# FAN_Board_Control_v1_040116.net
KiCad netlist of a schematic drawn in Altium Designer
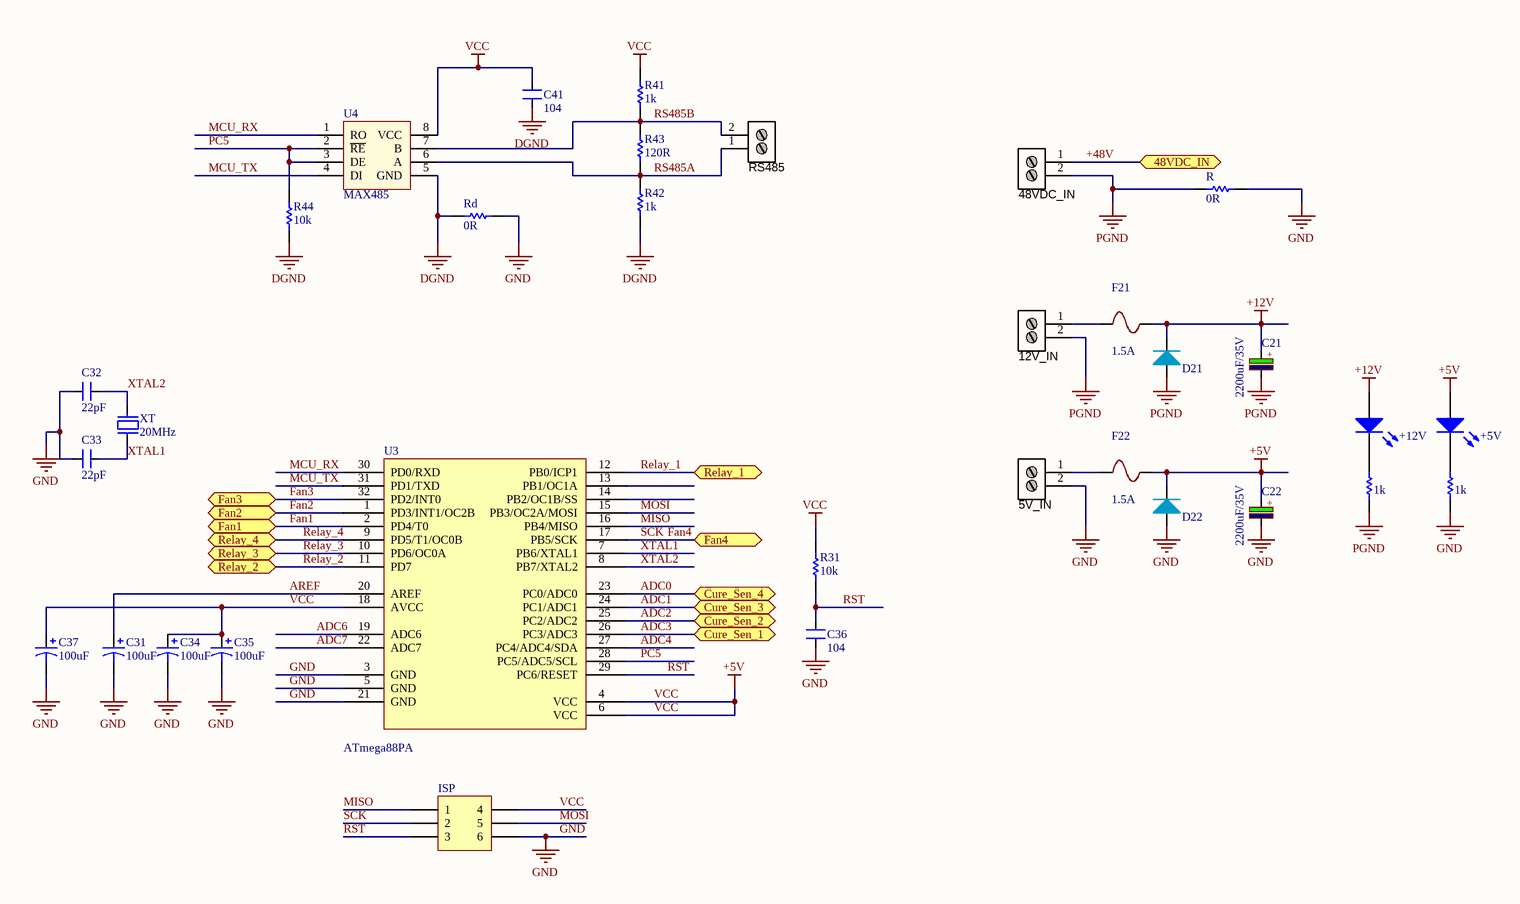
[diagram p0: FAN_Board_Control_v1_040116.SchDoc]

(export (version "E")
  (design (tool "Eeschema 10.0.6"))
  (components
    (comp (ref "+5V") (value "Led") (footprint "LED 5mm RED") (libsource (lib "Tuan") (part "Led")))
    (comp (ref "+12V") (value "Led") (footprint "LED 5mm RED") (libsource (lib "Tuan") (part "Led")))
    (comp (ref "5V_IN")
      (value "Stackable ScrewTerm")
      (footprint "2P_PCB_ScrewTerm_200mil")
      (description "Terminal Block Screw Type THT 2-Position 3.81mm pitch")
      (libsource (lib "PBL - Connectors") (part "2P_ScrewTerm_90S_3.81MM"))
    )
    (comp (ref "12V_IN")
      (value "Stackable ScrewTerm")
      (footprint "2P_PCB_ScrewTerm_200mil")
      (description "Terminal Block Screw Type THT 2-Position 3.81mm pitch")
      (libsource (lib "PBL - Connectors") (part "2P_ScrewTerm_90S_3.81MM"))
    )
    (comp (ref "48VDC_IN")
      (value "Stackable ScrewTerm")
      (footprint "2P_PCB_ScrewTerm_200mil")
      (description "Terminal Block Screw Type THT 2-Position 3.81mm pitch")
      (libsource (lib "PBL - Connectors") (part "2P_ScrewTerm_90S_3.81MM"))
    )
    (comp (ref "C21")
      (value "2200uF/35V")
      (footprint "heromap:CP_1000uF_25V")
      (description "Cap 1000uF/16V - 220uF/50V")
      (libsource (lib "heromap") (part "CP4"))
    )
    (comp (ref "C22")
      (value "2200uF/35V")
      (footprint "heromap:CP_1000uF_25V")
      (description "Cap 1000uF/16V - 220uF/50V")
      (libsource (lib "heromap") (part "CP4"))
    )
    (comp (ref "C31")
      (value "100uF")
      (footprint "CAPC2012N_F")
      (fields (field (name "Comment") "Cap"))
      (libsource (lib "Tuan") (part "Cap"))
    )
    (comp (ref "C32")
      (value "22pF")
      (footprint "CAPC1608N")
      (fields (field (name "Comment") "CAP NP"))
      (libsource (lib "Tuan") (part "CAP NP"))
    )
    (comp (ref "C33")
      (value "22pF")
      (footprint "CAPC1608N")
      (fields (field (name "Comment") "CAP NP"))
      (libsource (lib "Tuan") (part "CAP NP"))
    )
    (comp (ref "C34")
      (value "100uF")
      (footprint "CAPC2012N_F")
      (fields (field (name "Comment") "Cap"))
      (libsource (lib "Tuan") (part "Cap"))
    )
    (comp (ref "C35")
      (value "100uF")
      (footprint "CAPC2012N_F")
      (fields (field (name "Comment") "Cap"))
      (libsource (lib "Tuan") (part "Cap"))
    )
    (comp (ref "C36")
      (value "104")
      (footprint "CAPC1608N")
      (fields (field (name "Comment") "CAP NP"))
      (libsource (lib "Tuan") (part "CAP NP"))
    )
    (comp (ref "C37")
      (value "100uF")
      (footprint "CAPC2012N_F")
      (fields (field (name "Comment") "Cap"))
      (libsource (lib "Tuan") (part "Cap"))
    )
    (comp (ref "C41")
      (value "104")
      (footprint "CAPC2012N_F")
      (fields (field (name "Comment") "100nF/104"))
      (libsource (lib "Tuan") (part "CAP NP"))
    )
    (comp (ref "D21") (value "Diode") (footprint "DO-214AC") (libsource (lib "Tuan") (part "Diode")))
    (comp (ref "D22") (value "Diode") (footprint "DO-214AC") (libsource (lib "Tuan") (part "Diode")))
    (comp (ref "F21") (value "1.5A") (footprint "FUSE_SR-5-BK") (libsource (lib "Tuan") (part "Fuse")))
    (comp (ref "F22") (value "1.5A") (footprint "FUSE_SR-5-BK") (libsource (lib "Tuan") (part "Fuse")))
    (comp (ref "ISP")
      (value "Header 3X2A")
      (footprint "HDR2X3_CEN")
      (description "Header, 3-Pin, Dual row")
      (fields (field (name "PUBLISHER") "Altium Limited"))
      (libsource (lib "Miscellaneous Connectors") (part "Header 3X2A"))
    )
    (comp (ref "R")
      (value "0R")
      (footprint "RESTH_AXIAL-0.4")
      (fields (field (name "Comment") "Res"))
      (libsource (lib "Tuan") (part "Res"))
    )
    (comp (ref "R21")
      (value "1k")
      (footprint "RESC2012N_F")
      (fields (field (name "Comment") "Res_0805_1k"))
      (libsource (lib "Tuan") (part "Res"))
    )
    (comp (ref "R22")
      (value "1k")
      (footprint "RESC2012N_F")
      (fields (field (name "Comment") "Res_0805_1k"))
      (libsource (lib "Tuan") (part "Res"))
    )
    (comp (ref "R31")
      (value "10k")
      (footprint "RESC1608N_ZERO")
      (fields (field (name "Comment") "Res"))
      (libsource (lib "Tuan") (part "Res"))
    )
    (comp (ref "R41")
      (value "1k")
      (footprint "RESC2012N_F")
      (description "Tro dan")
      (libsource (lib "GPS_Clock_v12") (part "Res"))
    )
    (comp (ref "R42")
      (value "1k")
      (footprint "RESC2012N_F")
      (description "Tro dan")
      (libsource (lib "GPS_Clock_v12") (part "Res"))
    )
    (comp (ref "R43")
      (value "120R")
      (footprint "RESC2012N_F")
      (description "Tro dan")
      (fields (field (name "Comment") "330R"))
      (libsource (lib "GPS_Clock_v12") (part "Res"))
    )
    (comp (ref "R44")
      (value "10k")
      (footprint "RESC2012N_F")
      (description "Tro dan")
      (fields (field (name "Comment") "330R"))
      (libsource (lib "GPS_Clock_v12") (part "Res"))
    )
    (comp (ref "Rd")
      (value "0R")
      (footprint "RESC2012N_F")
      (fields (field (name "Comment") "Res"))
      (libsource (lib "Tuan") (part "Res"))
    )
    (comp (ref "RS485")
      (value "Stackable ScrewTerm")
      (footprint "2P_PCB1")
      (description "Terminal Block Screw Type THT 2-Position 3.81mm pitch")
      (libsource (lib "") (part "2P_ScrewTerm_90S_3.81MM_1"))
    )
    (comp (ref "U3")
      (value "ATmega88PA")
      (footprint "32PIN")
      (description "ATmega48/168/328")
      (libsource (lib "Tuan") (part "ATmega48/168/328"))
    )
    (comp (ref "U4")
      (value "MAX485")
      (footprint "SO-8")
      (description "RS232 - RS485 (Same sn75176)")
      (libsource (lib "heromap") (part "MAX485"))
    )
    (comp (ref "XT") (value "20MHz") (footprint "XT2") (libsource (lib "Tuan") (part "Crystal")))
  )
  (nets
    (net (code "1") (name "+5V") (class "Default")
      (node (ref "+5V") (pin "1") (pinfunction "A_1") (pintype "passive"))
      (node (ref "C22") (pin "1") (pinfunction "1_1") (pintype "passive"))
      (node (ref "C34") (pin "1") (pinfunction "1_1") (pintype "passive"))
      (node (ref "C35") (pin "1") (pinfunction "1_1") (pintype "passive"))
      (node (ref "C37") (pin "1") (pinfunction "1_1") (pintype "passive"))
      (node (ref "C41") (pin "2") (pinfunction "2_2") (pintype "passive"))
      (node (ref "D22") (pin "2") (pinfunction "K_2") (pintype "passive"))
      (node (ref "F22") (pin "2") (pinfunction "2_2") (pintype "passive"))
      (node (ref "ISP") (pin "4") (pinfunction "4_4") (pintype "passive"))
      (node (ref "R31") (pin "2") (pinfunction "2_2") (pintype "passive"))
      (node (ref "R41") (pin "2") (pinfunction "2_2") (pintype "passive"))
      (node (ref "U3") (pin "18") (pinfunction "AVCC_18") (pintype "passive"))
      (node (ref "U3") (pin "4") (pinfunction "VCC_4") (pintype "passive"))
      (node (ref "U3") (pin "6") (pinfunction "VCC_6") (pintype "passive"))
      (node (ref "U4") (pin "8") (pinfunction "VCC_8") (pintype "passive"))
    )
    (net (code "2") (name "+12V") (class "Default")
      (node (ref "+12V") (pin "1") (pinfunction "A_1") (pintype "passive"))
      (node (ref "C21") (pin "1") (pinfunction "1_1") (pintype "passive"))
      (node (ref "D21") (pin "2") (pinfunction "K_2") (pintype "passive"))
      (node (ref "F21") (pin "2") (pinfunction "2_2") (pintype "passive"))
    )
    (net (code "3") (name "/+48V") (class "Default")
      (node (ref "48VDC_IN") (pin "1") (pinfunction "1_1") (pintype "passive"))
    )
    (net (code "4") (name "/ADC0") (class "Default")
      (node (ref "U3") (pin "23") (pinfunction "PC0/ADC0_23") (pintype "passive"))
    )
    (net (code "5") (name "/ADC1") (class "Default")
      (node (ref "U3") (pin "24") (pinfunction "PC1/ADC1_24") (pintype "passive"))
    )
    (net (code "6") (name "/ADC2") (class "Default")
      (node (ref "U3") (pin "25") (pinfunction "PC2/ADC2_25") (pintype "passive"))
    )
    (net (code "7") (name "/ADC3") (class "Default")
      (node (ref "U3") (pin "26") (pinfunction "PC3/ADC3_26") (pintype "passive"))
    )
    (net (code "8") (name "/ADC4") (class "Default")
      (node (ref "U3") (pin "27") (pinfunction "PC4/ADC4/SDA_27") (pintype "passive"))
    )
    (net (code "9") (name "/ADC6") (class "Default")
      (node (ref "U3") (pin "19") (pinfunction "ADC6_19") (pintype "passive"))
    )
    (net (code "10") (name "/ADC7") (class "Default")
      (node (ref "U3") (pin "22") (pinfunction "ADC7_22") (pintype "passive"))
    )
    (net (code "11") (name "/AREF") (class "Default")
      (node (ref "C31") (pin "1") (pinfunction "1_1") (pintype "passive"))
      (node (ref "U3") (pin "20") (pinfunction "AREF_20") (pintype "passive"))
    )
    (net (code "12") (name "/Fan1") (class "Default")
      (node (ref "U3") (pin "2") (pinfunction "PD4/T0_2") (pintype "passive"))
    )
    (net (code "13") (name "/Fan2") (class "Default")
      (node (ref "U3") (pin "1") (pinfunction "PD3/INT1/OC2B_1") (pintype "passive"))
    )
    (net (code "14") (name "/Fan3") (class "Default")
      (node (ref "U3") (pin "32") (pinfunction "PD2/INT0_32") (pintype "passive"))
    )
    (net (code "15") (name "/Fan4") (class "Default")
      (node (ref "ISP") (pin "2") (pinfunction "2_2") (pintype "passive"))
      (node (ref "U3") (pin "17") (pinfunction "PB5/SCK_17") (pintype "passive"))
    )
    (net (code "16") (name "/MCU_RX") (class "Default")
      (node (ref "U3") (pin "30") (pinfunction "PD0/RXD_30") (pintype "passive"))
      (node (ref "U4") (pin "1") (pinfunction "RO_1") (pintype "passive"))
    )
    (net (code "17") (name "/MCU_TX") (class "Default")
      (node (ref "U3") (pin "31") (pinfunction "PD1/TXD_31") (pintype "passive"))
      (node (ref "U4") (pin "4") (pinfunction "DI_4") (pintype "passive"))
    )
    (net (code "18") (name "/MISO") (class "Default")
      (node (ref "ISP") (pin "1") (pinfunction "1_1") (pintype "passive"))
      (node (ref "U3") (pin "16") (pinfunction "PB4/MISO_16") (pintype "passive"))
    )
    (net (code "19") (name "/MOSI") (class "Default")
      (node (ref "ISP") (pin "5") (pinfunction "5_5") (pintype "passive"))
      (node (ref "U3") (pin "15") (pinfunction "PB3/OC2A/MOSI_15") (pintype "passive"))
    )
    (net (code "20") (name "/PC5") (class "Default")
      (node (ref "R44") (pin "2") (pinfunction "2_2") (pintype "passive"))
      (node (ref "U3") (pin "28") (pinfunction "PC5/ADC5/SCL_28") (pintype "passive"))
      (node (ref "U4") (pin "2") (pinfunction "~{RE}_2") (pintype "passive"))
      (node (ref "U4") (pin "3") (pinfunction "DE_3") (pintype "passive"))
    )
    (net (code "21") (name "/RS485A") (class "Default")
      (node (ref "R42") (pin "2") (pinfunction "2_2") (pintype "passive"))
      (node (ref "R43") (pin "1") (pinfunction "1_1") (pintype "passive"))
      (node (ref "RS485") (pin "1") (pinfunction "1_1") (pintype "passive"))
      (node (ref "U4") (pin "6") (pinfunction "A_6") (pintype "passive"))
    )
    (net (code "22") (name "/RS485B") (class "Default")
      (node (ref "R41") (pin "1") (pinfunction "1_1") (pintype "passive"))
      (node (ref "R43") (pin "2") (pinfunction "2_2") (pintype "passive"))
      (node (ref "RS485") (pin "2") (pinfunction "2_2") (pintype "passive"))
      (node (ref "U4") (pin "7") (pinfunction "B_7") (pintype "passive"))
    )
    (net (code "23") (name "/RST") (class "Default")
      (node (ref "C36") (pin "2") (pinfunction "2_2") (pintype "passive"))
      (node (ref "ISP") (pin "3") (pinfunction "3_3") (pintype "passive"))
      (node (ref "R31") (pin "1") (pinfunction "1_1") (pintype "passive"))
      (node (ref "U3") (pin "29") (pinfunction "PC6/RESET_29") (pintype "passive"))
    )
    (net (code "24") (name "/Relay_1") (class "Default")
      (node (ref "U3") (pin "12") (pinfunction "PB0/ICP1_12") (pintype "passive"))
    )
    (net (code "25") (name "/Relay_2") (class "Default")
      (node (ref "U3") (pin "11") (pinfunction "PD7_11") (pintype "passive"))
    )
    (net (code "26") (name "/Relay_3") (class "Default")
      (node (ref "U3") (pin "10") (pinfunction "PD6/OC0A_10") (pintype "passive"))
    )
    (net (code "27") (name "/Relay_4") (class "Default")
      (node (ref "U3") (pin "9") (pinfunction "PD5/T1/OC0B_9") (pintype "passive"))
    )
    (net (code "28") (name "/XTAL1") (class "Default")
      (node (ref "C33") (pin "1") (pinfunction "1_1") (pintype "passive"))
      (node (ref "U3") (pin "7") (pinfunction "PB6/XTAL1_7") (pintype "passive"))
      (node (ref "XT") (pin "1") (pinfunction "1_1") (pintype "passive"))
    )
    (net (code "29") (name "/XTAL2") (class "Default")
      (node (ref "C32") (pin "1") (pinfunction "1_1") (pintype "passive"))
      (node (ref "U3") (pin "8") (pinfunction "PB7/XTAL2_8") (pintype "passive"))
      (node (ref "XT") (pin "2") (pinfunction "2_2") (pintype "passive"))
    )
    (net (code "30") (name "DGND") (class "Default")
      (node (ref "C41") (pin "1") (pinfunction "1_1") (pintype "passive"))
      (node (ref "R42") (pin "1") (pinfunction "1_1") (pintype "passive"))
      (node (ref "R44") (pin "1") (pinfunction "1_1") (pintype "passive"))
      (node (ref "Rd") (pin "1") (pinfunction "1_1") (pintype "passive"))
      (node (ref "U4") (pin "5") (pinfunction "GND_5") (pintype "passive"))
    )
    (net (code "31") (name "GND") (class "Default")
      (node (ref "5V_IN") (pin "2") (pinfunction "2_2") (pintype "passive"))
      (node (ref "C22") (pin "2") (pinfunction "2_2") (pintype "passive"))
      (node (ref "C31") (pin "2") (pinfunction "2_2") (pintype "passive"))
      (node (ref "C32") (pin "2") (pinfunction "2_2") (pintype "passive"))
      (node (ref "C33") (pin "2") (pinfunction "2_2") (pintype "passive"))
      (node (ref "C34") (pin "2") (pinfunction "2_2") (pintype "passive"))
      (node (ref "C35") (pin "2") (pinfunction "2_2") (pintype "passive"))
      (node (ref "C36") (pin "1") (pinfunction "1_1") (pintype "passive"))
      (node (ref "C37") (pin "2") (pinfunction "2_2") (pintype "passive"))
      (node (ref "D22") (pin "1") (pinfunction "A_1") (pintype "passive"))
      (node (ref "ISP") (pin "6") (pinfunction "6_6") (pintype "passive"))
      (node (ref "R") (pin "2") (pinfunction "2_2") (pintype "passive"))
      (node (ref "R22") (pin "2") (pinfunction "2_2") (pintype "passive"))
      (node (ref "Rd") (pin "2") (pinfunction "2_2") (pintype "passive"))
      (node (ref "U3") (pin "21") (pinfunction "GND_21") (pintype "power_in"))
      (node (ref "U3") (pin "3") (pinfunction "GND_3") (pintype "power_in"))
      (node (ref "U3") (pin "5") (pinfunction "GND_5") (pintype "power_in"))
    )
    (net (code "32") (name "Net-(+5V-K)") (class "Default")
      (node (ref "+5V") (pin "2") (pinfunction "K_2") (pintype "passive"))
      (node (ref "R22") (pin "1") (pinfunction "1_1") (pintype "passive"))
    )
    (net (code "33") (name "Net-(+12V-K)") (class "Default")
      (node (ref "+12V") (pin "2") (pinfunction "K_2") (pintype "passive"))
      (node (ref "R21") (pin "1") (pinfunction "1_1") (pintype "passive"))
    )
    (net (code "34") (name "Net-(5V_IN-Pad1)") (class "Default")
      (node (ref "5V_IN") (pin "1") (pinfunction "1_1") (pintype "passive"))
      (node (ref "F22") (pin "1") (pinfunction "1_1") (pintype "passive"))
    )
    (net (code "35") (name "Net-(12V_IN-Pad1)") (class "Default")
      (node (ref "12V_IN") (pin "1") (pinfunction "1_1") (pintype "passive"))
      (node (ref "F21") (pin "1") (pinfunction "1_1") (pintype "passive"))
    )
    (net (code "36") (name "PGND") (class "Default")
      (node (ref "12V_IN") (pin "2") (pinfunction "2_2") (pintype "passive"))
      (node (ref "48VDC_IN") (pin "2") (pinfunction "2_2") (pintype "passive"))
      (node (ref "C21") (pin "2") (pinfunction "2_2") (pintype "passive"))
      (node (ref "D21") (pin "1") (pinfunction "A_1") (pintype "passive"))
      (node (ref "R") (pin "1") (pinfunction "1_1") (pintype "passive"))
      (node (ref "R21") (pin "2") (pinfunction "2_2") (pintype "passive"))
    )
    (net (code "37") (name "unconnected-(U3-PB1{slash}OC1A-Pad13)") (class "Default")
      (node (ref "U3") (pin "13") (pinfunction "PB1/OC1A_13") (pintype "passive"))
    )
    (net (code "38") (name "unconnected-(U3-PB2{slash}OC1B{slash}SS-Pad14)") (class "Default")
      (node (ref "U3") (pin "14") (pinfunction "PB2/OC1B/SS_14") (pintype "passive"))
    )
  )
)
